# EE209_Schematic.net
KiCad netlist of a schematic drawn in Altium Designer
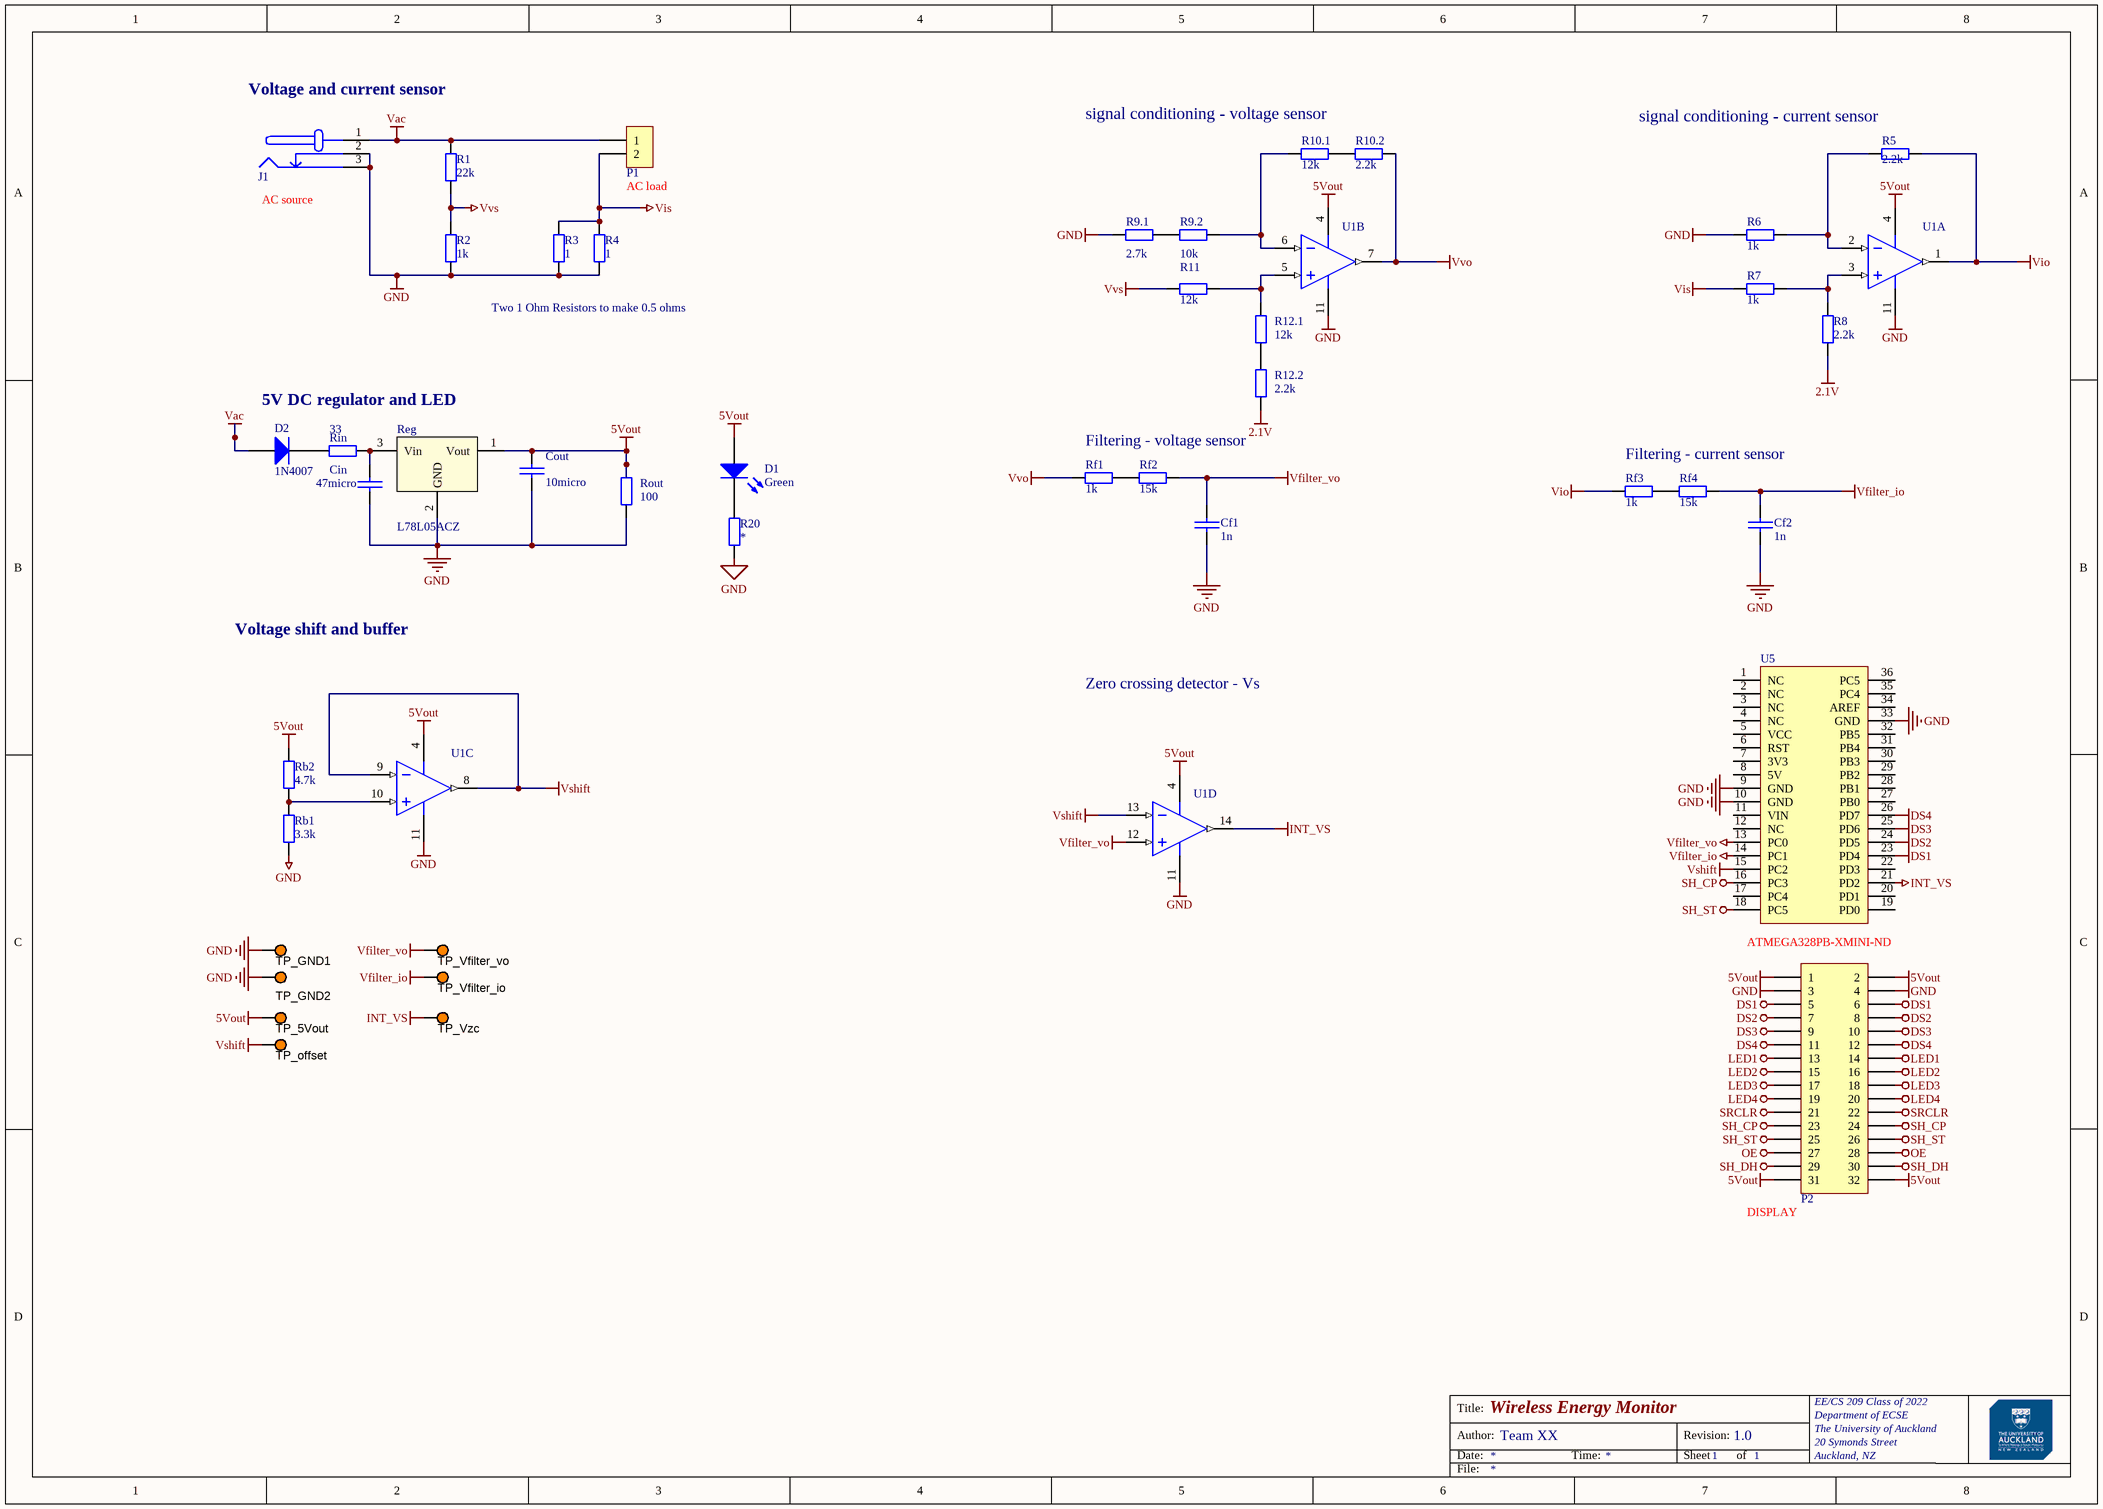
[diagram p0: EE209_Schematic.SchDoc]

(export (version "E")
  (design (tool "Eeschema 10.0.6"))
  (components
    (comp (ref "Cf1")
      (value "1n")
      (footprint "CCAP-5P0")
      (description "TH ceramic capacitor with 5mm pitch")
      (libsource (lib "EE209_Library") (part "CerCap_TH_5P0"))
    )
    (comp (ref "Cf2")
      (value "1n")
      (footprint "CCAP-5P0")
      (description "TH ceramic capacitor with 5mm pitch")
      (libsource (lib "EE209_Library") (part "CerCap_TH_5P0"))
    )
    (comp (ref "Cin")
      (value "47micro")
      (footprint "CCAP-5P0")
      (description "TH ceramic capacitor with 5mm pitch")
      (libsource (lib "EE209_Library") (part "CerCap_TH_5P0"))
    )
    (comp (ref "Cout")
      (value "10micro")
      (footprint "CCAP-5P0")
      (description "TH ceramic capacitor with 5mm pitch")
      (libsource (lib "EE209_Library") (part "CerCap_TH_5P0"))
    )
    (comp (ref "D1")
      (value "Green")
      (footprint "LED")
      (description "Typical throughole GaAs LED with 2.54mm pitch")
      (fields (field (name "MANUFACTURER") "Generic Components") (field (name "PUBLISHER") "Altium Limited"))
      (libsource (lib "EE209_Library") (part "LED_TH_2P54"))
    )
    (comp (ref "D2")
      (value "1N4007")
      (footprint "1N4007-MFG")
      (description "1N4007 1000V standard axial diode")
      (libsource (lib "EE209_Library") (part "1N4007_TH_4AX0"))
    )
    (comp (ref "J1")
      (value "DC barrel jack")
      (footprint "AC-Socket")
      (description "DC barrel jack connection to AC source")
      (libsource (lib "EE209_Library") (part "AC_Input"))
    )
    (comp (ref "P1")
      (value "Dual Banana Plugs")
      (footprint "Dual Banana Plug")
      (description "Dual banana plugs connection to the AC load")
      (fields (field (name "PUBLISHER") "Altium Limited"))
      (libsource (lib "EE209_Library") (part "AC_Output"))
    )
    (comp (ref "P2")
      (value "Display")
      (footprint "Display")
      (description "16-Pin Header Connecting Display")
      (libsource (lib "EE209_Library") (part "Display"))
    )
    (comp (ref "R1")
      (value "22k")
      (footprint "AXIAL-0.4")
      (description "Through hole resistor")
      (fields (field (name "PUBLISHER") "Altium Limited"))
      (libsource (lib "EE209_Library") (part "Res_TH_0AX4"))
    )
    (comp (ref "R2")
      (value "1k")
      (footprint "AXIAL-0.4")
      (description "Through hole resistor")
      (fields (field (name "PUBLISHER") "Altium Limited"))
      (libsource (lib "EE209_Library") (part "Res_TH_0AX4"))
    )
    (comp (ref "R3")
      (value "1")
      (footprint "AXIAL-0.4")
      (description "Through hole resistor")
      (fields (field (name "PUBLISHER") "Altium Limited"))
      (libsource (lib "EE209_Library") (part "Res_TH_0AX4"))
    )
    (comp (ref "R4")
      (value "1")
      (footprint "AXIAL-0.4")
      (description "Through hole resistor")
      (fields (field (name "PUBLISHER") "Altium Limited"))
      (libsource (lib "EE209_Library") (part "Res_TH_0AX4"))
    )
    (comp (ref "R5")
      (value "2.2k")
      (footprint "AXIAL-0.4")
      (description "Through hole resistor")
      (fields (field (name "PUBLISHER") "Altium Limited"))
      (libsource (lib "") (part "Res_TH_0AX4_1"))
    )
    (comp (ref "R6")
      (value "1k")
      (footprint "AXIAL-0.4")
      (description "Through hole resistor")
      (fields (field (name "PUBLISHER") "Altium Limited"))
      (libsource (lib "") (part "Res_TH_0AX4_1"))
    )
    (comp (ref "R7")
      (value "1k")
      (footprint "AXIAL-0.4")
      (description "Through hole resistor")
      (fields (field (name "PUBLISHER") "Altium Limited"))
      (libsource (lib "") (part "Res_TH_0AX4_1"))
    )
    (comp (ref "R8")
      (value "2.2k")
      (footprint "AXIAL-0.4")
      (description "Through hole resistor")
      (fields (field (name "PUBLISHER") "Altium Limited"))
      (libsource (lib "EE209_Library") (part "Res_TH_0AX4"))
    )
    (comp (ref "R9.1")
      (value "2.7k")
      (footprint "AXIAL-0.4")
      (description "Through hole resistor")
      (fields (field (name "PUBLISHER") "Altium Limited"))
      (libsource (lib "") (part "Res_TH_0AX4_1"))
    )
    (comp (ref "R9.2")
      (value "10k")
      (footprint "AXIAL-0.4")
      (description "Through hole resistor")
      (fields (field (name "PUBLISHER") "Altium Limited"))
      (libsource (lib "") (part "Res_TH_0AX4_1"))
    )
    (comp (ref "R10.1")
      (value "12k")
      (footprint "AXIAL-0.4")
      (description "Through hole resistor")
      (fields (field (name "PUBLISHER") "Altium Limited"))
      (libsource (lib "") (part "Res_TH_0AX4_1"))
    )
    (comp (ref "R10.2")
      (value "2.2k")
      (footprint "AXIAL-0.4")
      (description "Through hole resistor")
      (fields (field (name "PUBLISHER") "Altium Limited"))
      (libsource (lib "") (part "Res_TH_0AX4_1"))
    )
    (comp (ref "R11")
      (value "12k")
      (footprint "AXIAL-0.4")
      (description "Through hole resistor")
      (fields (field (name "PUBLISHER") "Altium Limited"))
      (libsource (lib "") (part "Res_TH_0AX4_1"))
    )
    (comp (ref "R12.1")
      (value "12k")
      (footprint "AXIAL-0.4")
      (description "Through hole resistor")
      (fields (field (name "PUBLISHER") "Altium Limited"))
      (libsource (lib "EE209_Library") (part "Res_TH_0AX4"))
    )
    (comp (ref "R12.2")
      (value "2.2k")
      (footprint "AXIAL-0.4")
      (description "Through hole resistor")
      (fields (field (name "PUBLISHER") "Altium Limited"))
      (libsource (lib "EE209_Library") (part "Res_TH_0AX4"))
    )
    (comp (ref "R20")
      (value "*")
      (footprint "AXIAL-0.4")
      (description "Through hole resistor")
      (fields (field (name "PUBLISHER") "Altium Limited"))
      (libsource (lib "EE209_Library") (part "Res_TH_0AX4"))
    )
    (comp (ref "Rb1")
      (value "3.3k")
      (footprint "AXIAL-0.4")
      (description "Through hole resistor")
      (fields (field (name "PUBLISHER") "Altium Limited"))
      (libsource (lib "EE209_Library") (part "Res_TH_0AX4"))
    )
    (comp (ref "Rb2")
      (value "4.7k")
      (footprint "AXIAL-0.4")
      (description "Through hole resistor")
      (fields (field (name "PUBLISHER") "Altium Limited"))
      (libsource (lib "EE209_Library") (part "Res_TH_0AX4"))
    )
    (comp (ref "Reg")
      (value "L78L05ACZ")
      (footprint "TO-92")
      (description "Voltage Regulator 5V")
      (fields
        (field (name "MANUFACTURER") "ON Semiconductor")
        (field (name "MANUFACTURER PART NUMBER") "LM78L05ACZX")
      )
      (libsource (lib "EE209_Library") (part "L78L05_TH_TO92"))
    )
    (comp (ref "Rf1")
      (value "1k")
      (footprint "AXIAL-0.4")
      (description "Through hole resistor")
      (fields (field (name "PUBLISHER") "Altium Limited"))
      (libsource (lib "") (part "Res_TH_0AX4_1"))
    )
    (comp (ref "Rf2")
      (value "15k")
      (footprint "AXIAL-0.4")
      (description "Through hole resistor")
      (fields (field (name "PUBLISHER") "Altium Limited"))
      (libsource (lib "") (part "Res_TH_0AX4_1"))
    )
    (comp (ref "Rf3")
      (value "1k")
      (footprint "AXIAL-0.4")
      (description "Through hole resistor")
      (fields (field (name "PUBLISHER") "Altium Limited"))
      (libsource (lib "") (part "Res_TH_0AX4_1"))
    )
    (comp (ref "Rf4")
      (value "15k")
      (footprint "AXIAL-0.4")
      (description "Through hole resistor")
      (fields (field (name "PUBLISHER") "Altium Limited"))
      (libsource (lib "") (part "Res_TH_0AX4_1"))
    )
    (comp (ref "Rin")
      (value "33")
      (footprint "AXIAL-0.4")
      (description "Through hole resistor")
      (fields (field (name "PUBLISHER") "Altium Limited"))
      (libsource (lib "") (part "Res_TH_0AX4_1"))
    )
    (comp (ref "Rout")
      (value "100")
      (footprint "AXIAL-0.4")
      (description "Through hole resistor")
      (fields (field (name "PUBLISHER") "Altium Limited"))
      (libsource (lib "EE209_Library") (part "Res_TH_0AX4"))
    )
    (comp (ref "TP_5Vout")
      (value "5003")
      (footprint "TP_TH")
      (description "Test Point, Orange, 1-Pin THD, RoHS")
      (libsource (lib "EE209_Library") (part "TestPoint"))
    )
    (comp (ref "TP_GND1")
      (value "5003")
      (footprint "TP_TH")
      (description "Test Point, Orange, 1-Pin THD, RoHS")
      (libsource (lib "EE209_Library") (part "TestPoint"))
    )
    (comp (ref "TP_GND2")
      (value "5003")
      (footprint "TP_TH")
      (description "Test Point, Orange, 1-Pin THD, RoHS")
      (libsource (lib "EE209_Library") (part "TestPoint"))
    )
    (comp (ref "TP_offset")
      (value "5003")
      (footprint "TP_TH")
      (description "Test Point, Orange, 1-Pin THD, RoHS")
      (libsource (lib "EE209_Library") (part "TestPoint"))
    )
    (comp (ref "TP_Vfilter_io")
      (value "5003")
      (footprint "TP_TH")
      (description "Test Point, Orange, 1-Pin THD, RoHS")
      (libsource (lib "EE209_Library") (part "TestPoint"))
    )
    (comp (ref "TP_Vfilter_vo")
      (value "5003")
      (footprint "TP_TH")
      (description "Test Point, Orange, 1-Pin THD, RoHS")
      (libsource (lib "EE209_Library") (part "TestPoint"))
    )
    (comp (ref "TP_Vzc")
      (value "5003")
      (footprint "TP_TH")
      (description "Test Point, Orange, 1-Pin THD, RoHS")
      (libsource (lib "EE209_Library") (part "TestPoint"))
    )
    (comp (ref "U1")
      (value "LM324")
      (footprint "DIP-14")
      (description "IC OPAMP GP 14DIP")
      (fields
        (field (name "MANUFACTURER") "ON Semiconductor")
        (field (name "MANUFACTURER PART NUMBER") "LM324N")
      )
      (libsource (lib "EE209_Library") (part "LM324N_TH_DIP16"))
    )
    (comp (ref "U5")
      (value "ATmega328PB Xplained Mini Header")
      (footprint "ATmeg328P Xplained")
      (description "Dual 18-pin headers connecting to ATmega328PB Xplained Mini")
      (fields
        (field (name "MANUFACTURER") "Microchip Technology")
        (field (name "MANUFACTURER PART NUMBER") "ATMEGA328PB-XMINI")
        (field (name "SUPPLIER PART NUMBER 1") "ATMEGA328PB-XMINI-ND")
      )
      (libsource (lib "EE209_Library") (part "ATmega328PBXplained_TH"))
    )
  )
  (nets
    (net (code "1") (name "2.1V") (class "Default")
      (node (ref "R12.2") (pin "1") (pinfunction "1_1") (pintype "passive"))
      (node (ref "R8") (pin "1") (pinfunction "1_1") (pintype "passive"))
    )
    (net (code "2") (name "5Vout") (class "Default")
      (node (ref "Cout") (pin "1") (pinfunction "1_1") (pintype "passive"))
      (node (ref "D1") (pin "1") (pinfunction "A_1") (pintype "passive"))
      (node (ref "P2") (pin "1") (pinfunction "1_1") (pintype "passive"))
      (node (ref "P2") (pin "2") (pinfunction "2_2") (pintype "passive"))
      (node (ref "P2") (pin "31") (pinfunction "31_31") (pintype "passive"))
      (node (ref "P2") (pin "32") (pinfunction "32_32") (pintype "passive"))
      (node (ref "Rb2") (pin "2") (pinfunction "2_2") (pintype "passive"))
      (node (ref "Reg") (pin "1") (pinfunction "Vout_1") (pintype "passive"))
      (node (ref "Rout") (pin "2") (pinfunction "2_2") (pintype "passive"))
      (node (ref "TP_5Vout") (pin "1") (pinfunction "1_1") (pintype "passive"))
      (node (ref "U1") (pin "4") (pinfunction "VDD_4") (pintype "power_in"))
    )
    (net (code "3") (name "DS1") (class "Default")
      (node (ref "P2") (pin "5") (pinfunction "5_5") (pintype "passive"))
      (node (ref "P2") (pin "6") (pinfunction "6_6") (pintype "passive"))
      (node (ref "U5") (pin "23") (pinfunction "PD4_23") (pintype "passive"))
    )
    (net (code "4") (name "DS2") (class "Default")
      (node (ref "P2") (pin "7") (pinfunction "7_7") (pintype "passive"))
      (node (ref "P2") (pin "8") (pinfunction "8_8") (pintype "passive"))
      (node (ref "U5") (pin "24") (pinfunction "PD5_24") (pintype "passive"))
    )
    (net (code "5") (name "DS3") (class "Default")
      (node (ref "P2") (pin "10") (pinfunction "10_10") (pintype "passive"))
      (node (ref "P2") (pin "9") (pinfunction "9_9") (pintype "passive"))
      (node (ref "U5") (pin "25") (pinfunction "PD6_25") (pintype "passive"))
    )
    (net (code "6") (name "DS4") (class "Default")
      (node (ref "P2") (pin "11") (pinfunction "11_11") (pintype "passive"))
      (node (ref "P2") (pin "12") (pinfunction "12_12") (pintype "passive"))
      (node (ref "U5") (pin "26") (pinfunction "PD7_26") (pintype "passive"))
    )
    (net (code "7") (name "GND") (class "Default")
      (node (ref "Cf1") (pin "2") (pinfunction "2_2") (pintype "passive"))
      (node (ref "Cf2") (pin "2") (pinfunction "2_2") (pintype "passive"))
      (node (ref "Cin") (pin "2") (pinfunction "2_2") (pintype "passive"))
      (node (ref "Cout") (pin "2") (pinfunction "2_2") (pintype "passive"))
      (node (ref "J1") (pin "2") (pinfunction "GND_ALT_2") (pintype "power_in"))
      (node (ref "J1") (pin "3") (pinfunction "GND_3") (pintype "power_in"))
      (node (ref "P2") (pin "3") (pinfunction "3_3") (pintype "passive"))
      (node (ref "P2") (pin "4") (pinfunction "4_4") (pintype "passive"))
      (node (ref "R2") (pin "1") (pinfunction "1_1") (pintype "passive"))
      (node (ref "R20") (pin "1") (pinfunction "1_1") (pintype "passive"))
      (node (ref "R3") (pin "1") (pinfunction "1_1") (pintype "passive"))
      (node (ref "R4") (pin "1") (pinfunction "1_1") (pintype "passive"))
      (node (ref "R6") (pin "1") (pinfunction "1_1") (pintype "passive"))
      (node (ref "R9.1") (pin "1") (pinfunction "1_1") (pintype "passive"))
      (node (ref "Rb1") (pin "1") (pinfunction "1_1") (pintype "passive"))
      (node (ref "Reg") (pin "2") (pinfunction "GND_2") (pintype "passive"))
      (node (ref "Rout") (pin "1") (pinfunction "1_1") (pintype "passive"))
      (node (ref "TP_GND1") (pin "1") (pinfunction "1_1") (pintype "passive"))
      (node (ref "TP_GND2") (pin "1") (pinfunction "1_1") (pintype "passive"))
      (node (ref "U1") (pin "11") (pinfunction "VSS_11") (pintype "power_in"))
      (node (ref "U5") (pin "10") (pinfunction "GND_10") (pintype "power_in"))
      (node (ref "U5") (pin "33") (pinfunction "GND_33") (pintype "passive"))
      (node (ref "U5") (pin "9") (pinfunction "GND_9") (pintype "power_in"))
    )
    (net (code "8") (name "INT_VS") (class "Default")
      (node (ref "TP_Vzc") (pin "1") (pinfunction "1_1") (pintype "passive"))
      (node (ref "U1") (pin "14") (pinfunction "VOUTD_14") (pintype "output"))
      (node (ref "U5") (pin "21") (pinfunction "PD2_21") (pintype "passive"))
    )
    (net (code "9") (name "LED1") (class "Default")
      (node (ref "P2") (pin "13") (pinfunction "13_13") (pintype "passive"))
      (node (ref "P2") (pin "14") (pinfunction "14_14") (pintype "passive"))
    )
    (net (code "10") (name "LED2") (class "Default")
      (node (ref "P2") (pin "15") (pinfunction "15_15") (pintype "passive"))
      (node (ref "P2") (pin "16") (pinfunction "16_16") (pintype "passive"))
    )
    (net (code "11") (name "LED3") (class "Default")
      (node (ref "P2") (pin "17") (pinfunction "17_17") (pintype "passive"))
      (node (ref "P2") (pin "18") (pinfunction "18_18") (pintype "passive"))
    )
    (net (code "12") (name "LED4") (class "Default")
      (node (ref "P2") (pin "19") (pinfunction "19_19") (pintype "passive"))
      (node (ref "P2") (pin "20") (pinfunction "20_20") (pintype "passive"))
    )
    (net (code "13") (name "Net-(D1-K)") (class "Default")
      (node (ref "D1") (pin "2") (pinfunction "K_2") (pintype "passive"))
      (node (ref "R20") (pin "2") (pinfunction "2_2") (pintype "passive"))
    )
    (net (code "14") (name "Net-(D2-K)") (class "Default")
      (node (ref "D2") (pin "2") (pinfunction "K_2") (pintype "passive"))
      (node (ref "Rin") (pin "1") (pinfunction "1_1") (pintype "passive"))
    )
    (net (code "15") (name "Net-(R9.1-Pad2)") (class "Default")
      (node (ref "R9.1") (pin "2") (pinfunction "2_2") (pintype "passive"))
      (node (ref "R9.2") (pin "1") (pinfunction "1_1") (pintype "passive"))
    )
    (net (code "16") (name "Net-(R10.1-Pad2)") (class "Default")
      (node (ref "R10.1") (pin "2") (pinfunction "2_2") (pintype "passive"))
      (node (ref "R10.2") (pin "1") (pinfunction "1_1") (pintype "passive"))
    )
    (net (code "17") (name "Net-(R12.1-Pad1)") (class "Default")
      (node (ref "R12.1") (pin "1") (pinfunction "1_1") (pintype "passive"))
      (node (ref "R12.2") (pin "2") (pinfunction "2_2") (pintype "passive"))
    )
    (net (code "18") (name "Net-(Reg-Vin)") (class "Default")
      (node (ref "Cin") (pin "1") (pinfunction "1_1") (pintype "passive"))
      (node (ref "Reg") (pin "3") (pinfunction "Vin_3") (pintype "passive"))
      (node (ref "Rin") (pin "2") (pinfunction "2_2") (pintype "passive"))
    )
    (net (code "19") (name "Net-(Rf1-Pad2)") (class "Default")
      (node (ref "Rf1") (pin "2") (pinfunction "2_2") (pintype "passive"))
      (node (ref "Rf2") (pin "1") (pinfunction "1_1") (pintype "passive"))
    )
    (net (code "20") (name "Net-(Rf3-Pad2)") (class "Default")
      (node (ref "Rf3") (pin "2") (pinfunction "2_2") (pintype "passive"))
      (node (ref "Rf4") (pin "1") (pinfunction "1_1") (pintype "passive"))
    )
    (net (code "21") (name "Net-(U1A-VINA+)") (class "Default")
      (node (ref "R7") (pin "2") (pinfunction "2_2") (pintype "passive"))
      (node (ref "R8") (pin "2") (pinfunction "2_2") (pintype "passive"))
      (node (ref "U1") (pin "3") (pinfunction "VINA+_3") (pintype "input"))
    )
    (net (code "22") (name "Net-(U1A-VINA-)") (class "Default")
      (node (ref "R5") (pin "1") (pinfunction "1_1") (pintype "passive"))
      (node (ref "R6") (pin "2") (pinfunction "2_2") (pintype "passive"))
      (node (ref "U1") (pin "2") (pinfunction "VINA-_2") (pintype "input"))
    )
    (net (code "23") (name "Net-(U1B-VINB+)") (class "Default")
      (node (ref "R11") (pin "2") (pinfunction "2_2") (pintype "passive"))
      (node (ref "R12.1") (pin "2") (pinfunction "2_2") (pintype "passive"))
      (node (ref "U1") (pin "5") (pinfunction "VINB+_5") (pintype "input"))
    )
    (net (code "24") (name "Net-(U1B-VINB-)") (class "Default")
      (node (ref "R10.1") (pin "1") (pinfunction "1_1") (pintype "passive"))
      (node (ref "R9.2") (pin "2") (pinfunction "2_2") (pintype "passive"))
      (node (ref "U1") (pin "6") (pinfunction "VINB-_6") (pintype "input"))
    )
    (net (code "25") (name "Net-(U1C-VINC+)") (class "Default")
      (node (ref "Rb1") (pin "2") (pinfunction "2_2") (pintype "passive"))
      (node (ref "Rb2") (pin "1") (pinfunction "1_1") (pintype "passive"))
      (node (ref "U1") (pin "10") (pinfunction "VINC+_10") (pintype "input"))
    )
    (net (code "26") (name "OE") (class "Default")
      (node (ref "P2") (pin "27") (pinfunction "27_27") (pintype "passive"))
      (node (ref "P2") (pin "28") (pinfunction "28_28") (pintype "passive"))
    )
    (net (code "27") (name "SH_CP") (class "Default")
      (node (ref "P2") (pin "23") (pinfunction "23_23") (pintype "passive"))
      (node (ref "P2") (pin "24") (pinfunction "24_24") (pintype "passive"))
      (node (ref "U5") (pin "16") (pinfunction "PC3_16") (pintype "passive"))
    )
    (net (code "28") (name "SH_DH") (class "Default")
      (node (ref "P2") (pin "29") (pinfunction "29_29") (pintype "passive"))
      (node (ref "P2") (pin "30") (pinfunction "30_30") (pintype "passive"))
    )
    (net (code "29") (name "SH_ST") (class "Default")
      (node (ref "P2") (pin "25") (pinfunction "25_25") (pintype "passive"))
      (node (ref "P2") (pin "26") (pinfunction "26_26") (pintype "passive"))
      (node (ref "U5") (pin "18") (pinfunction "PC5_18") (pintype "passive"))
    )
    (net (code "30") (name "SRCLR") (class "Default")
      (node (ref "P2") (pin "21") (pinfunction "21_21") (pintype "passive"))
      (node (ref "P2") (pin "22") (pinfunction "22_22") (pintype "passive"))
    )
    (net (code "31") (name "Vac") (class "Default")
      (node (ref "D2") (pin "1") (pinfunction "A_1") (pintype "passive"))
      (node (ref "J1") (pin "1") (pinfunction "VCC_1") (pintype "power_in"))
      (node (ref "P1") (pin "1") (pinfunction "1_1") (pintype "passive"))
      (node (ref "R1") (pin "2") (pinfunction "2_2") (pintype "passive"))
    )
    (net (code "32") (name "Vfilter_io") (class "Default")
      (node (ref "Cf2") (pin "1") (pinfunction "1_1") (pintype "passive"))
      (node (ref "Rf4") (pin "2") (pinfunction "2_2") (pintype "passive"))
      (node (ref "TP_Vfilter_io") (pin "1") (pinfunction "1_1") (pintype "passive"))
      (node (ref "U5") (pin "14") (pinfunction "PC1_14") (pintype "passive"))
    )
    (net (code "33") (name "Vfilter_vo") (class "Default")
      (node (ref "Cf1") (pin "1") (pinfunction "1_1") (pintype "passive"))
      (node (ref "Rf2") (pin "2") (pinfunction "2_2") (pintype "passive"))
      (node (ref "TP_Vfilter_vo") (pin "1") (pinfunction "1_1") (pintype "passive"))
      (node (ref "U1") (pin "12") (pinfunction "VIND+_12") (pintype "input"))
      (node (ref "U5") (pin "13") (pinfunction "PC0_13") (pintype "passive"))
    )
    (net (code "34") (name "Vio") (class "Default")
      (node (ref "R5") (pin "2") (pinfunction "2_2") (pintype "passive"))
      (node (ref "Rf3") (pin "1") (pinfunction "1_1") (pintype "passive"))
      (node (ref "U1") (pin "1") (pinfunction "VOUTA_1") (pintype "output"))
    )
    (net (code "35") (name "Vis") (class "Default")
      (node (ref "P1") (pin "2") (pinfunction "2_2") (pintype "passive"))
      (node (ref "R3") (pin "2") (pinfunction "2_2") (pintype "passive"))
      (node (ref "R4") (pin "2") (pinfunction "2_2") (pintype "passive"))
      (node (ref "R7") (pin "1") (pinfunction "1_1") (pintype "passive"))
    )
    (net (code "36") (name "Vshift") (class "Default")
      (node (ref "TP_offset") (pin "1") (pinfunction "1_1") (pintype "passive"))
      (node (ref "U1") (pin "13") (pinfunction "VIND-_13") (pintype "input"))
      (node (ref "U1") (pin "8") (pinfunction "VOUTC_8") (pintype "output"))
      (node (ref "U1") (pin "9") (pinfunction "VINC-_9") (pintype "input"))
      (node (ref "U5") (pin "15") (pinfunction "PC2_15") (pintype "passive"))
    )
    (net (code "37") (name "Vvo") (class "Default")
      (node (ref "R10.2") (pin "2") (pinfunction "2_2") (pintype "passive"))
      (node (ref "Rf1") (pin "1") (pinfunction "1_1") (pintype "passive"))
      (node (ref "U1") (pin "7") (pinfunction "VOUTB_7") (pintype "output"))
    )
    (net (code "38") (name "Vvs") (class "Default")
      (node (ref "R1") (pin "1") (pinfunction "1_1") (pintype "passive"))
      (node (ref "R11") (pin "1") (pinfunction "1_1") (pintype "passive"))
      (node (ref "R2") (pin "2") (pinfunction "2_2") (pintype "passive"))
    )
    (net (code "39") (name "unconnected-(U5-3V3-Pad7)") (class "Default")
      (node (ref "U5") (pin "7") (pinfunction "3V3_7") (pintype "passive"))
    )
    (net (code "40") (name "unconnected-(U5-5V-Pad8)") (class "Default")
      (node (ref "U5") (pin "8") (pinfunction "5V_8") (pintype "power_in"))
    )
    (net (code "41") (name "unconnected-(U5-AREF-Pad34)") (class "Default")
      (node (ref "U5") (pin "34") (pinfunction "AREF_34") (pintype "passive"))
    )
    (net (code "42") (name "unconnected-(U5-NC-Pad1)") (class "Default")
      (node (ref "U5") (pin "1") (pinfunction "NC_1") (pintype "passive"))
    )
    (net (code "43") (name "unconnected-(U5-NC-Pad2)") (class "Default")
      (node (ref "U5") (pin "2") (pinfunction "NC_2") (pintype "passive"))
    )
    (net (code "44") (name "unconnected-(U5-NC-Pad3)") (class "Default")
      (node (ref "U5") (pin "3") (pinfunction "NC_3") (pintype "passive"))
    )
    (net (code "45") (name "unconnected-(U5-NC-Pad4)") (class "Default")
      (node (ref "U5") (pin "4") (pinfunction "NC_4") (pintype "passive"))
    )
    (net (code "46") (name "unconnected-(U5-NC-Pad12)") (class "Default")
      (node (ref "U5") (pin "12") (pinfunction "NC_12") (pintype "passive"))
    )
    (net (code "47") (name "unconnected-(U5-PB0-Pad27)") (class "Default")
      (node (ref "U5") (pin "27") (pinfunction "PB0_27") (pintype "passive"))
    )
    (net (code "48") (name "unconnected-(U5-PB1-Pad28)") (class "Default")
      (node (ref "U5") (pin "28") (pinfunction "PB1_28") (pintype "passive"))
    )
    (net (code "49") (name "unconnected-(U5-PB2-Pad29)") (class "Default")
      (node (ref "U5") (pin "29") (pinfunction "PB2_29") (pintype "passive"))
    )
    (net (code "50") (name "unconnected-(U5-PB3-Pad30)") (class "Default")
      (node (ref "U5") (pin "30") (pinfunction "PB3_30") (pintype "passive"))
    )
    (net (code "51") (name "unconnected-(U5-PB4-Pad31)") (class "Default")
      (node (ref "U5") (pin "31") (pinfunction "PB4_31") (pintype "passive"))
    )
    (net (code "52") (name "unconnected-(U5-PB5-Pad32)") (class "Default")
      (node (ref "U5") (pin "32") (pinfunction "PB5_32") (pintype "passive"))
    )
    (net (code "53") (name "unconnected-(U5-PC4-Pad17)") (class "Default")
      (node (ref "U5") (pin "17") (pinfunction "PC4_17") (pintype "passive"))
    )
    (net (code "54") (name "unconnected-(U5-PC4-Pad35)") (class "Default")
      (node (ref "U5") (pin "35") (pinfunction "PC4_35") (pintype "passive"))
    )
    (net (code "55") (name "unconnected-(U5-PC5-Pad36)") (class "Default")
      (node (ref "U5") (pin "36") (pinfunction "PC5_36") (pintype "passive"))
    )
    (net (code "56") (name "unconnected-(U5-PD0-Pad19)") (class "Default")
      (node (ref "U5") (pin "19") (pinfunction "PD0_19") (pintype "passive"))
    )
    (net (code "57") (name "unconnected-(U5-PD1-Pad20)") (class "Default")
      (node (ref "U5") (pin "20") (pinfunction "PD1_20") (pintype "passive"))
    )
    (net (code "58") (name "unconnected-(U5-PD3-Pad22)") (class "Default")
      (node (ref "U5") (pin "22") (pinfunction "PD3_22") (pintype "passive"))
    )
    (net (code "59") (name "unconnected-(U5-RST-Pad6)") (class "Default")
      (node (ref "U5") (pin "6") (pinfunction "RST_6") (pintype "passive"))
    )
    (net (code "60") (name "unconnected-(U5-VCC-Pad5)") (class "Default")
      (node (ref "U5") (pin "5") (pinfunction "VCC_5") (pintype "power_in"))
    )
    (net (code "61") (name "unconnected-(U5-VIN-Pad11)") (class "Default")
      (node (ref "U5") (pin "11") (pinfunction "VIN_11") (pintype "power_in"))
    )
  )
)
